# ADC.net
KiCad netlist of a schematic drawn in Altium Designer
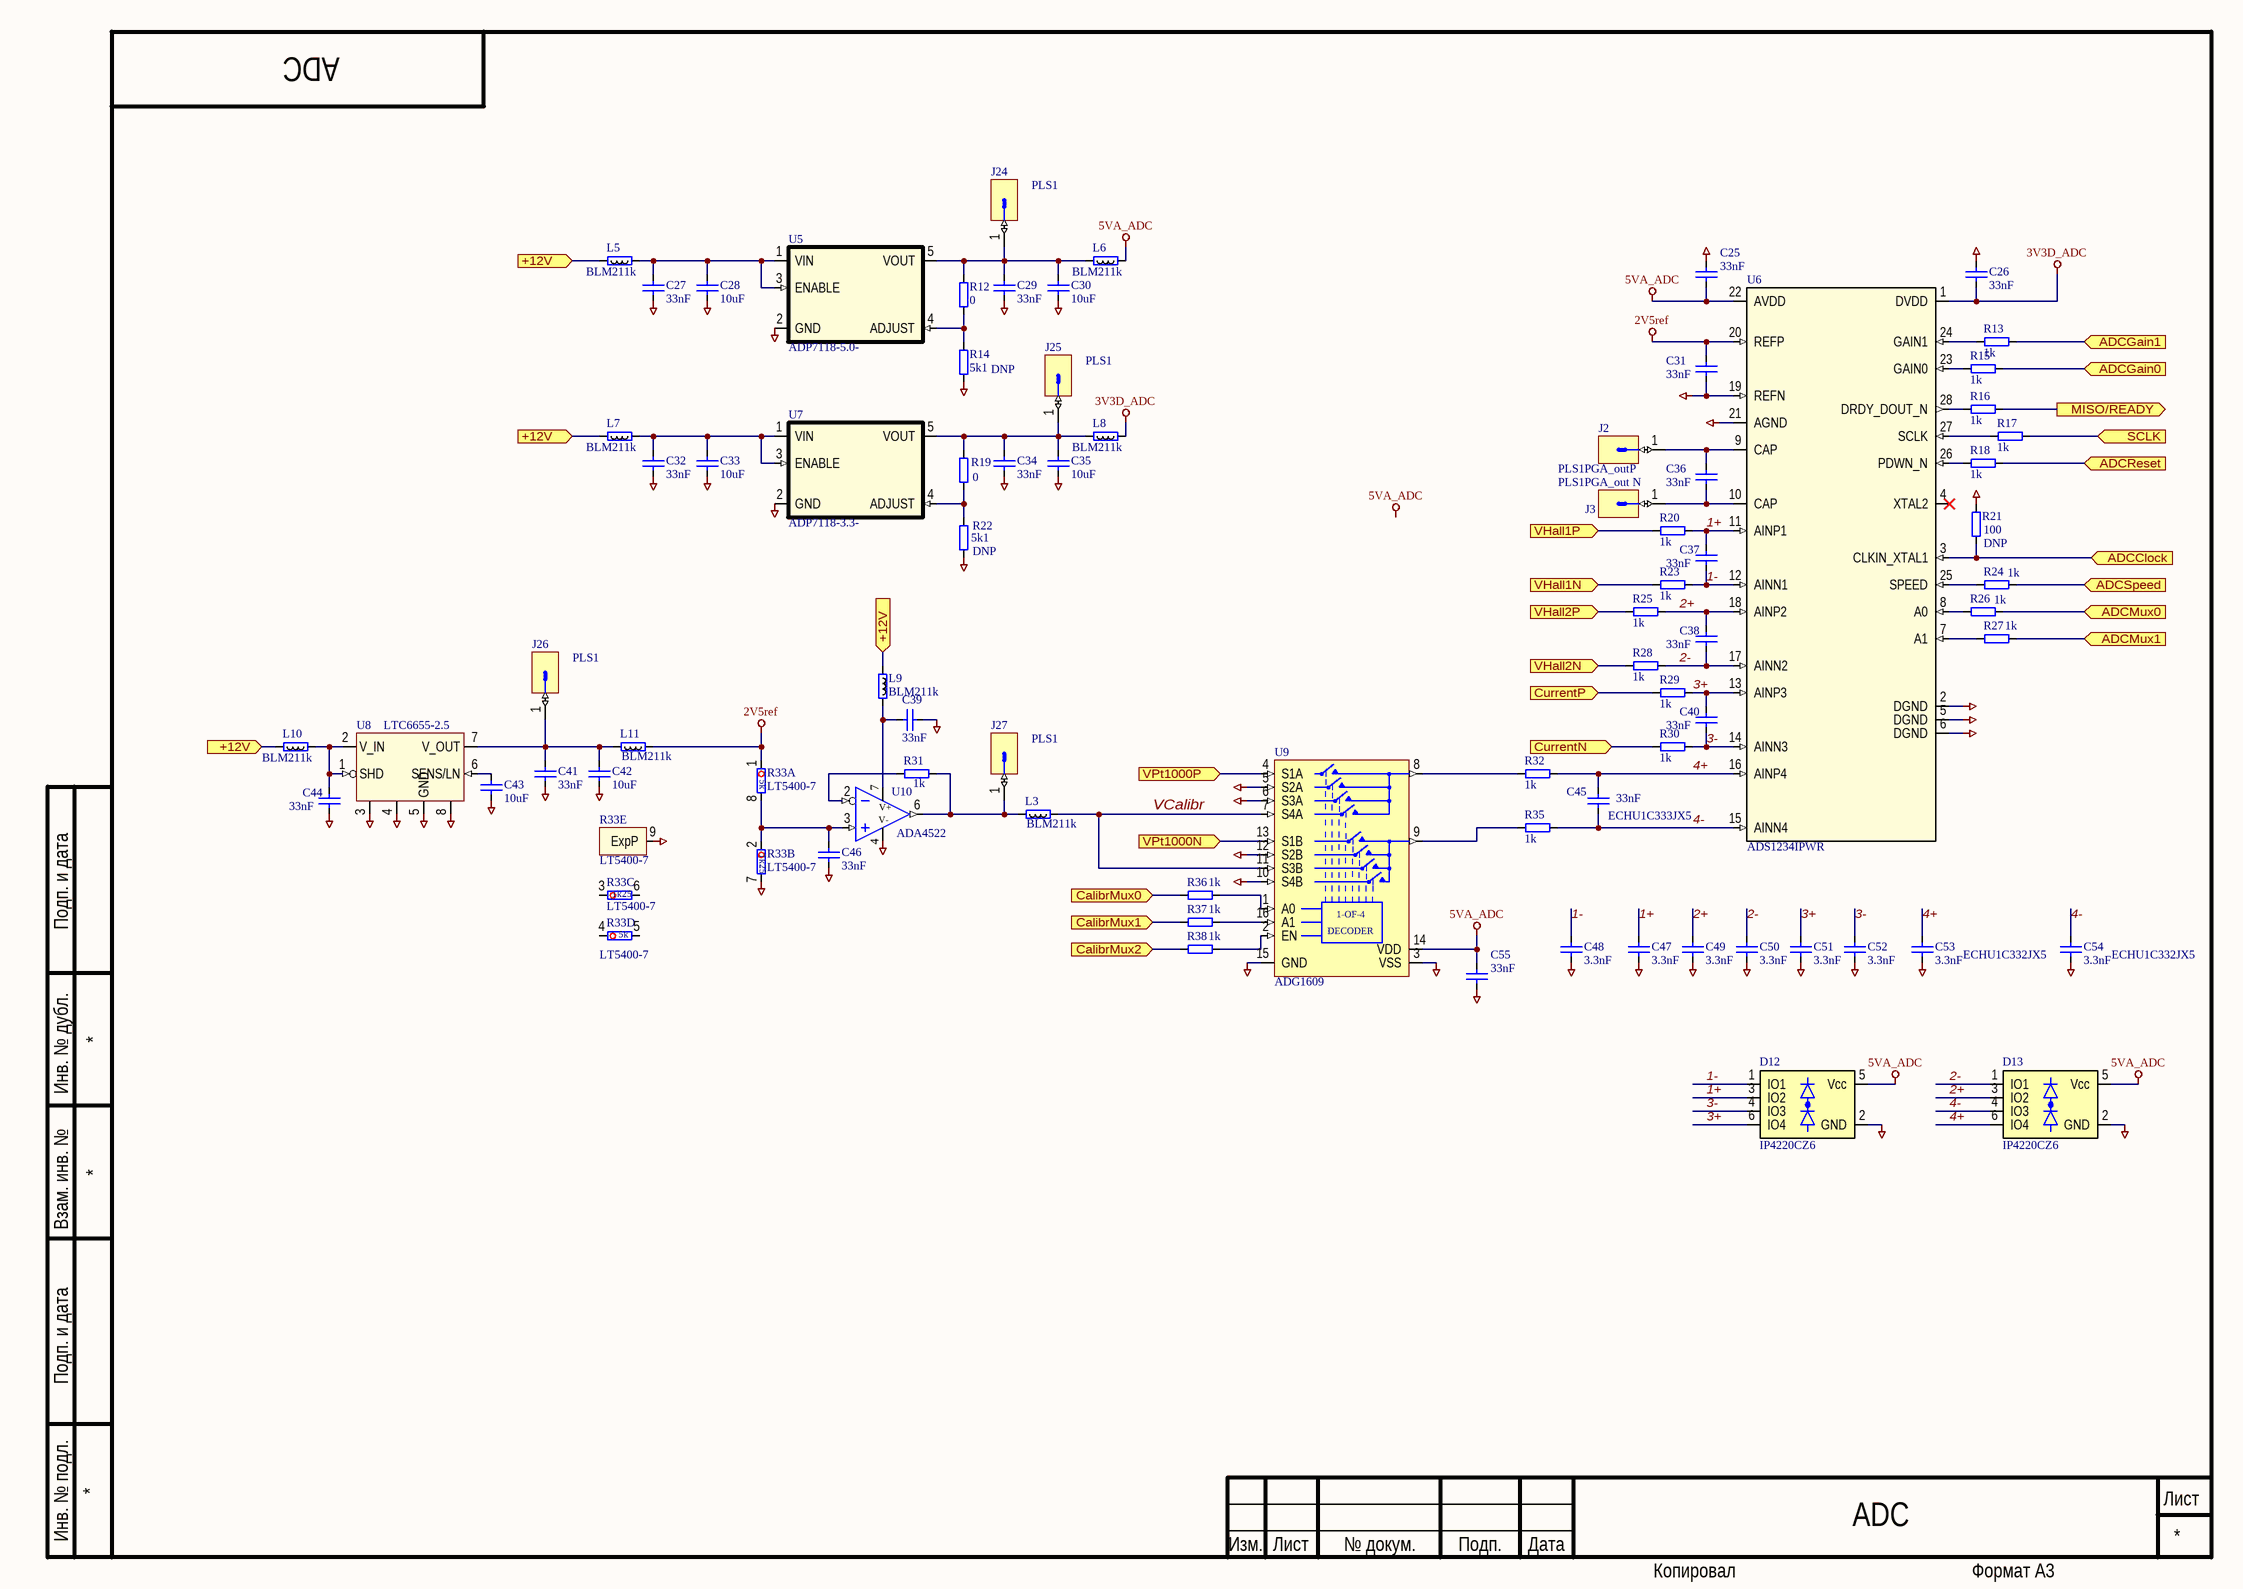
[diagram p0: ADC.SchDoc]

(export (version "E")
  (design (tool "Eeschema 10.0.6"))
  (components
    (comp (ref "C25")
      (value "33nF")
      (footprint "CAPC1608X87N")
      (description "Чип конденсатор 0603")
      (fields (field (name "VOLTAGE") "50V") (field (name "TOLERANCE") "20%"))
      (libsource (lib "DDSintLib") (part "C0603"))
    )
    (comp (ref "C26")
      (value "33nF")
      (footprint "CAPC1608X87N")
      (description "Чип конденсатор 0603")
      (fields (field (name "VOLTAGE") "50V") (field (name "TOLERANCE") "20%"))
      (libsource (lib "DDSintLib") (part "C0603"))
    )
    (comp (ref "C27")
      (value "33nF")
      (footprint "SMD0805CAP")
      (description "Чип конденсатор 0805")
      (fields (field (name "VOLTAGE") "25V") (field (name "TOLERANCE") "20%"))
      (libsource (lib "DDSintLib") (part "C0805"))
    )
    (comp (ref "C28")
      (value "10uF")
      (footprint "SMD0805CAP")
      (description "Чип конденсатор 0805")
      (fields (field (name "VOLTAGE") "25V") (field (name "TOLERANCE") "20%"))
      (libsource (lib "DDSintLib") (part "C0805"))
    )
    (comp (ref "C29")
      (value "33nF")
      (footprint "SMD0805CAP")
      (description "Чип конденсатор 0805")
      (fields (field (name "VOLTAGE") "25V") (field (name "TOLERANCE") "20%"))
      (libsource (lib "DDSintLib") (part "C0805"))
    )
    (comp (ref "C30")
      (value "10uF")
      (footprint "SMD0805CAP")
      (description "Чип конденсатор 0805")
      (fields (field (name "VOLTAGE") "25V") (field (name "TOLERANCE") "20%"))
      (libsource (lib "DDSintLib") (part "C0805"))
    )
    (comp (ref "C31")
      (value "33nF")
      (footprint "CAPC1608X87N")
      (description "Чип конденсатор 0603")
      (fields (field (name "VOLTAGE") "50V") (field (name "TOLERANCE") "20%"))
      (libsource (lib "DDSintLib") (part "C0603"))
    )
    (comp (ref "C32")
      (value "33nF")
      (footprint "SMD0805CAP")
      (description "Чип конденсатор 0805")
      (fields (field (name "VOLTAGE") "25V") (field (name "TOLERANCE") "20%"))
      (libsource (lib "DDSintLib") (part "C0805"))
    )
    (comp (ref "C33")
      (value "10uF")
      (footprint "SMD0805CAP")
      (description "Чип конденсатор 0805")
      (fields (field (name "VOLTAGE") "25V") (field (name "TOLERANCE") "20%"))
      (libsource (lib "DDSintLib") (part "C0805"))
    )
    (comp (ref "C34")
      (value "33nF")
      (footprint "SMD0805CAP")
      (description "Чип конденсатор 0805")
      (fields (field (name "VOLTAGE") "25V") (field (name "TOLERANCE") "20%"))
      (libsource (lib "DDSintLib") (part "C0805"))
    )
    (comp (ref "C35")
      (value "10uF")
      (footprint "SMD0805CAP")
      (description "Чип конденсатор 0805")
      (fields (field (name "VOLTAGE") "25V") (field (name "TOLERANCE") "20%"))
      (libsource (lib "DDSintLib") (part "C0805"))
    )
    (comp (ref "C36")
      (value "33nF")
      (footprint "CAPC1608X87N")
      (description "Чип конденсатор 0603")
      (fields (field (name "VOLTAGE") "50V") (field (name "TOLERANCE") "20%"))
      (libsource (lib "DDSintLib") (part "C0603"))
    )
    (comp (ref "C37")
      (value "33nF")
      (footprint "CAPC1608X87N")
      (description "Чип конденсатор 0603")
      (fields (field (name "VOLTAGE") "50V") (field (name "TOLERANCE") "20%"))
      (libsource (lib "DDSintLib") (part "C0603"))
    )
    (comp (ref "C38")
      (value "33nF")
      (footprint "CAPC1608X87N")
      (description "Чип конденсатор 0603")
      (fields (field (name "VOLTAGE") "50V") (field (name "TOLERANCE") "20%"))
      (libsource (lib "DDSintLib") (part "C0603"))
    )
    (comp (ref "C39")
      (value "33nF")
      (footprint "SMD0805CAP")
      (description "Чип конденсатор 0805")
      (fields (field (name "VOLTAGE") "25V") (field (name "TOLERANCE") "20%"))
      (libsource (lib "DDSintLib") (part "C0805"))
    )
    (comp (ref "C40")
      (value "33nF")
      (footprint "CAPC1608X87N")
      (description "Чип конденсатор 0603")
      (fields (field (name "VOLTAGE") "50V") (field (name "TOLERANCE") "20%"))
      (libsource (lib "DDSintLib") (part "C0603"))
    )
    (comp (ref "C41")
      (value "33nF")
      (footprint "SMD0805CAP")
      (description "Чип конденсатор 0805")
      (fields (field (name "VOLTAGE") "25V") (field (name "TOLERANCE") "20%"))
      (libsource (lib "DDSintLib") (part "C0805"))
    )
    (comp (ref "C42")
      (value "10uF")
      (footprint "SMD0805CAP")
      (description "Чип конденсатор 0805")
      (fields (field (name "VOLTAGE") "25V") (field (name "TOLERANCE") "20%"))
      (libsource (lib "DDSintLib") (part "C0805"))
    )
    (comp (ref "C43")
      (value "10uF")
      (footprint "SMD0805CAP")
      (description "Чип конденсатор 0805")
      (fields (field (name "VOLTAGE") "25V") (field (name "TOLERANCE") "20%"))
      (libsource (lib "DDSintLib") (part "C0805"))
    )
    (comp (ref "C44")
      (value "33nF")
      (footprint "SMD0805CAP")
      (description "Чип конденсатор 0805")
      (fields (field (name "VOLTAGE") "25V") (field (name "TOLERANCE") "20%"))
      (libsource (lib "DDSintLib") (part "C0805"))
    )
    (comp (ref "C45")
      (value "33nF")
      (footprint "CAPC1206")
      (description "Чип конденсатор 1206")
      (fields
        (field (name "VOLTAGE") "16V")
        (field (name "TOLERANCE") "1%")
        (field (name "NAME TO ORDER") "ECHU1C333JX5")
      )
      (libsource (lib "DDSintLib") (part "C1206"))
    )
    (comp (ref "C46")
      (value "33nF")
      (footprint "SMD0805CAP")
      (description "Чип конденсатор 0805")
      (fields (field (name "VOLTAGE") "25V") (field (name "TOLERANCE") "20%"))
      (libsource (lib "DDSintLib") (part "C0805"))
    )
    (comp (ref "C47")
      (value "3.3nF")
      (footprint "CAPC1608X87N")
      (description "Чип конденсатор 0603")
      (fields (field (name "VOLTAGE") "50V") (field (name "TOLERANCE") "20%"))
      (libsource (lib "DDSintLib") (part "C0603"))
    )
    (comp (ref "C48")
      (value "3.3nF")
      (footprint "CAPC1608X87N")
      (description "Чип конденсатор 0603")
      (fields (field (name "VOLTAGE") "50V") (field (name "TOLERANCE") "20%"))
      (libsource (lib "DDSintLib") (part "C0603"))
    )
    (comp (ref "C49")
      (value "3.3nF")
      (footprint "CAPC1608X87N")
      (description "Чип конденсатор 0603")
      (fields (field (name "VOLTAGE") "50V") (field (name "TOLERANCE") "20%"))
      (libsource (lib "DDSintLib") (part "C0603"))
    )
    (comp (ref "C50")
      (value "3.3nF")
      (footprint "CAPC1608X87N")
      (description "Чип конденсатор 0603")
      (fields (field (name "VOLTAGE") "50V") (field (name "TOLERANCE") "20%"))
      (libsource (lib "DDSintLib") (part "C0603"))
    )
    (comp (ref "C51")
      (value "3.3nF")
      (footprint "CAPC1608X87N")
      (description "Чип конденсатор 0603")
      (fields (field (name "VOLTAGE") "50V") (field (name "TOLERANCE") "20%"))
      (libsource (lib "DDSintLib") (part "C0603"))
    )
    (comp (ref "C52")
      (value "3.3nF")
      (footprint "CAPC1608X87N")
      (description "Чип конденсатор 0603")
      (fields (field (name "VOLTAGE") "50V") (field (name "TOLERANCE") "20%"))
      (libsource (lib "DDSintLib") (part "C0603"))
    )
    (comp (ref "C53")
      (value "3.3nF")
      (footprint "SMD0805CAP")
      (description "Чип конденсатор 0805")
      (fields
        (field (name "VOLTAGE") "25V")
        (field (name "TOLERANCE") "20%")
        (field (name "NAME TO ORDER") "ECHU1C332JX5")
      )
      (libsource (lib "DDSintLib") (part "C0805"))
    )
    (comp (ref "C54")
      (value "3.3nF")
      (footprint "SMD0805CAP")
      (description "Чип конденсатор 0805")
      (fields
        (field (name "VOLTAGE") "25V")
        (field (name "TOLERANCE") "20%")
        (field (name "NAME TO ORDER") "ECHU1C332JX5")
      )
      (libsource (lib "DDSintLib") (part "C0805"))
    )
    (comp (ref "C55")
      (value "33nF")
      (footprint "CAPC1608X87N")
      (description "Чип конденсатор 0603")
      (fields (field (name "VOLTAGE") "50V") (field (name "TOLERANCE") "20%"))
      (libsource (lib "DDSintLib") (part "C0603"))
    )
    (comp (ref "D12")
      (value "IP4220CZ6")
      (footprint "SOT95P270X145-6N")
      (description "Optotransistor")
      (fields (field (name "VOLTAGE") "6V"))
      (libsource (lib "DDSintLib") (part "IP4220"))
    )
    (comp (ref "D13")
      (value "IP4220CZ6")
      (footprint "SOT95P270X145-6N")
      (description "Optotransistor")
      (fields (field (name "VOLTAGE") "6V"))
      (libsource (lib "DDSintLib") (part "IP4220"))
    )
    (comp (ref "J2")
      (value "PLS1PGA_outP")
      (footprint "PLS1")
      (description "Штырь PLS1")
      (libsource (lib "") (part "PLS1_1"))
    )
    (comp (ref "J3")
      (value "PLS1PGA_out N")
      (footprint "PLS1")
      (description "Штырь PLS1")
      (libsource (lib "") (part "PLS1_1"))
    )
    (comp (ref "J24")
      (value "PLS1")
      (footprint "PLS1")
      (description "Штырь PLS1")
      (libsource (lib "DDSintLib") (part "PLS1"))
    )
    (comp (ref "J25")
      (value "PLS1")
      (footprint "PLS1")
      (description "Штырь PLS1")
      (libsource (lib "DDSintLib") (part "PLS1"))
    )
    (comp (ref "J26")
      (value "PLS1")
      (footprint "PLS1")
      (description "Штырь PLS1")
      (libsource (lib "DDSintLib") (part "PLS1"))
    )
    (comp (ref "J27")
      (value "PLS1")
      (footprint "PLS1")
      (description "Штырь PLS1")
      (libsource (lib "DDSintLib") (part "PLS1"))
    )
    (comp (ref "L3")
      (value "BLM211k")
      (footprint "RESC2012X50N")
      (description "SMD Ferrite bead 0805")
      (libsource (lib "DDSintLib") (part "BLM21"))
    )
    (comp (ref "L5")
      (value "BLM211k")
      (footprint "RESC2012X50N")
      (description "SMD Ferrite bead 0805")
      (libsource (lib "DDSintLib") (part "BLM21"))
    )
    (comp (ref "L6")
      (value "BLM211k")
      (footprint "RESC2012X50N")
      (description "SMD Ferrite bead 0805")
      (libsource (lib "DDSintLib") (part "BLM21"))
    )
    (comp (ref "L7")
      (value "BLM211k")
      (footprint "RESC2012X50N")
      (description "SMD Ferrite bead 0805")
      (libsource (lib "DDSintLib") (part "BLM21"))
    )
    (comp (ref "L8")
      (value "BLM211k")
      (footprint "RESC2012X50N")
      (description "SMD Ferrite bead 0805")
      (libsource (lib "DDSintLib") (part "BLM21"))
    )
    (comp (ref "L9")
      (value "BLM211k")
      (footprint "RESC2012X50N")
      (description "SMD Ferrite bead 0805")
      (libsource (lib "DDSintLib") (part "BLM21"))
    )
    (comp (ref "L10")
      (value "BLM211k")
      (footprint "RESC2012X50N")
      (description "SMD Ferrite bead 0805")
      (libsource (lib "DDSintLib") (part "BLM21"))
    )
    (comp (ref "L11")
      (value "BLM211k")
      (footprint "RESC2012X50N")
      (description "SMD Ferrite bead 0805")
      (libsource (lib "DDSintLib") (part "BLM21"))
    )
    (comp (ref "R12")
      (value "0")
      (footprint "SMD0805RES")
      (description "Чип резистор 0805")
      (fields (field (name "TOLERANCE") "1%"))
      (libsource (lib "DDSintLib") (part "R0805"))
    )
    (comp (ref "R13")
      (value "1k")
      (footprint "SMD0805RES")
      (description "Чип резистор 0805")
      (fields (field (name "TOLERANCE") "1%"))
      (libsource (lib "DDSintLib") (part "R0805"))
    )
    (comp (ref "R14")
      (value "5k1")
      (footprint "SMD0805RES")
      (description "Чип резистор 0805")
      (fields (field (name "SOLDER OPTION") "DNP") (field (name "TOLERANCE") "1%"))
      (libsource (lib "DDSintLib") (part "R0805"))
    )
    (comp (ref "R15")
      (value "1k")
      (footprint "SMD0805RES")
      (description "Чип резистор 0805")
      (fields (field (name "TOLERANCE") "1%"))
      (libsource (lib "DDSintLib") (part "R0805"))
    )
    (comp (ref "R16")
      (value "1k")
      (footprint "SMD0805RES")
      (description "Чип резистор 0805")
      (fields (field (name "TOLERANCE") "1%"))
      (libsource (lib "DDSintLib") (part "R0805"))
    )
    (comp (ref "R17")
      (value "1k")
      (footprint "SMD0805RES")
      (description "Чип резистор 0805")
      (fields (field (name "TOLERANCE") "1%"))
      (libsource (lib "DDSintLib") (part "R0805"))
    )
    (comp (ref "R18")
      (value "1k")
      (footprint "SMD0805RES")
      (description "Чип резистор 0805")
      (fields (field (name "TOLERANCE") "1%"))
      (libsource (lib "DDSintLib") (part "R0805"))
    )
    (comp (ref "R19")
      (value "0")
      (footprint "SMD0805RES")
      (description "Чип резистор 0805")
      (fields (field (name "TOLERANCE") "1%"))
      (libsource (lib "DDSintLib") (part "R0805"))
    )
    (comp (ref "R20")
      (value "1k")
      (footprint "SMD0805RES")
      (description "Чип резистор 0805")
      (fields (field (name "TOLERANCE") "1%"))
      (libsource (lib "DDSintLib") (part "R0805"))
    )
    (comp (ref "R21")
      (value "100")
      (footprint "SMD0805RES")
      (description "Чип резистор 0805")
      (fields (field (name "SOLDER OPTION") "DNP") (field (name "TOLERANCE") "1%"))
      (libsource (lib "DDSintLib") (part "R0805"))
    )
    (comp (ref "R22")
      (value "5k1")
      (footprint "SMD0805RES")
      (description "Чип резистор 0805")
      (fields (field (name "SOLDER OPTION") "DNP") (field (name "TOLERANCE") "1%"))
      (libsource (lib "DDSintLib") (part "R0805"))
    )
    (comp (ref "R23")
      (value "1k")
      (footprint "SMD0805RES")
      (description "Чип резистор 0805")
      (fields (field (name "TOLERANCE") "1%"))
      (libsource (lib "DDSintLib") (part "R0805"))
    )
    (comp (ref "R24")
      (value "1k")
      (footprint "SMD0805RES")
      (description "Чип резистор 0805")
      (fields (field (name "TOLERANCE") "1%"))
      (libsource (lib "DDSintLib") (part "R0805"))
    )
    (comp (ref "R25")
      (value "1k")
      (footprint "SMD0805RES")
      (description "Чип резистор 0805")
      (fields (field (name "TOLERANCE") "1%"))
      (libsource (lib "DDSintLib") (part "R0805"))
    )
    (comp (ref "R26")
      (value "1k")
      (footprint "SMD0805RES")
      (description "Чип резистор 0805")
      (fields (field (name "TOLERANCE") "1%"))
      (libsource (lib "DDSintLib") (part "R0805"))
    )
    (comp (ref "R27")
      (value "1k")
      (footprint "SMD0805RES")
      (description "Чип резистор 0805")
      (fields (field (name "TOLERANCE") "1%"))
      (libsource (lib "DDSintLib") (part "R0805"))
    )
    (comp (ref "R28")
      (value "1k")
      (footprint "SMD0805RES")
      (description "Чип резистор 0805")
      (fields (field (name "TOLERANCE") "1%"))
      (libsource (lib "DDSintLib") (part "R0805"))
    )
    (comp (ref "R29")
      (value "1k")
      (footprint "SMD0805RES")
      (description "Чип резистор 0805")
      (fields (field (name "TOLERANCE") "1%"))
      (libsource (lib "DDSintLib") (part "R0805"))
    )
    (comp (ref "R30")
      (value "1k")
      (footprint "SMD0805RES")
      (description "Чип резистор 0805")
      (fields (field (name "TOLERANCE") "1%"))
      (libsource (lib "DDSintLib") (part "R0805"))
    )
    (comp (ref "R31")
      (value "1k")
      (footprint "SMD0805RES")
      (description "Чип резистор 0805")
      (fields (field (name "TOLERANCE") "1%"))
      (libsource (lib "DDSintLib") (part "R0805"))
    )
    (comp (ref "R32")
      (value "1k")
      (footprint "SMD0805RES")
      (description "Чип резистор 0805")
      (fields (field (name "TOLERANCE") "1%"))
      (libsource (lib "DDSintLib") (part "R0805"))
    )
    (comp (ref "R33")
      (value "LT5400-7")
      (footprint "SOP65P488X110-9N-R178X241")
      (description "4 прецизионных резистора")
      (fields (field (name "TOLERANCE") "0..025%"))
      (libsource (lib "") (part "LT5400_7_1"))
    )
    (comp (ref "R35")
      (value "1k")
      (footprint "SMD0805RES")
      (description "Чип резистор 0805")
      (fields (field (name "TOLERANCE") "1%"))
      (libsource (lib "DDSintLib") (part "R0805"))
    )
    (comp (ref "R36")
      (value "1k")
      (footprint "SMD0805RES")
      (description "Чип резистор 0805")
      (fields (field (name "TOLERANCE") "1%"))
      (libsource (lib "DDSintLib") (part "R0805"))
    )
    (comp (ref "R37")
      (value "1k")
      (footprint "SMD0805RES")
      (description "Чип резистор 0805")
      (fields (field (name "TOLERANCE") "1%"))
      (libsource (lib "DDSintLib") (part "R0805"))
    )
    (comp (ref "R38")
      (value "1k")
      (footprint "SMD0805RES")
      (description "Чип резистор 0805")
      (fields (field (name "TOLERANCE") "1%"))
      (libsource (lib "DDSintLib") (part "R0805"))
    )
    (comp (ref "U5")
      (value "ADP7118-5.0-")
      (footprint "SOT23-5")
      (description "Positive LDO Linear stabilizer")
      (libsource (lib "DDSintLib") (part "ADP7118"))
    )
    (comp (ref "U6")
      (value "ADS1234IPWR")
      (footprint "SOP65P780X200-28N")
      (description "АЦП")
      (fields (field (name "VOLTAGE") "2V7 to 5V3"))
      (libsource (lib "DDS1") (part "ADS1234"))
    )
    (comp (ref "U7")
      (value "ADP7118-3.3-")
      (footprint "SOT23-5")
      (description "Positive LDO Linear stabilizer")
      (libsource (lib "DDSintLib") (part "ADP7118"))
    )
    (comp (ref "U8")
      (value "LTC6655-2.5")
      (footprint "DDS1:SOP65P488X110-8N")
      (description "Low noise precision reference,")
      (fields (field (name "VOLTAGE") "max13.2V"))
      (libsource (lib "DDS1") (part "LTC6655B-5"))
    )
    (comp (ref "U9")
      (value "ADG1609")
      (footprint "TSSOP-16")
      (description "Мультиплексор аналоговый дифференциальный 4 канала")
      (libsource (lib "DDSintLib") (part "ADG1609"))
    )
    (comp (ref "U10")
      (value "ADA4522")
      (footprint "SOP65P488X110-8N")
      (description "Op amp")
      (fields (field (name "VOLTAGE") "+-5 to +-27.5V"))
      (libsource (lib "DDS1") (part "ADA4522"))
    )
  )
  (nets
    (net (code "1") (name "/+12V") (class "Default")
      (node (ref "L10") (pin "1") (pinfunction "1_1") (pintype "passive"))
      (node (ref "L5") (pin "1") (pinfunction "1_1") (pintype "passive"))
      (node (ref "L7") (pin "1") (pinfunction "1_1") (pintype "passive"))
      (node (ref "L9") (pin "2") (pinfunction "2_2") (pintype "passive"))
    )
    (net (code "2") (name "/1+") (class "Default")
      (node (ref "C37") (pin "2") (pinfunction "2_2") (pintype "passive"))
      (node (ref "C47") (pin "2") (pinfunction "2_2") (pintype "passive"))
      (node (ref "D12") (pin "3") (pinfunction "IO2_3") (pintype "passive"))
      (node (ref "R20") (pin "2") (pinfunction "2_2") (pintype "passive"))
      (node (ref "U6") (pin "11") (pinfunction "AINP1_11") (pintype "input"))
    )
    (net (code "3") (name "/1-") (class "Default")
      (node (ref "C37") (pin "1") (pinfunction "1_1") (pintype "passive"))
      (node (ref "C48") (pin "2") (pinfunction "2_2") (pintype "passive"))
      (node (ref "D12") (pin "1") (pinfunction "IO1_1") (pintype "passive"))
      (node (ref "R23") (pin "2") (pinfunction "2_2") (pintype "passive"))
      (node (ref "U6") (pin "12") (pinfunction "AINN1_12") (pintype "input"))
    )
    (net (code "4") (name "/2+") (class "Default")
      (node (ref "C38") (pin "2") (pinfunction "2_2") (pintype "passive"))
      (node (ref "C49") (pin "2") (pinfunction "2_2") (pintype "passive"))
      (node (ref "D13") (pin "3") (pinfunction "IO2_3") (pintype "passive"))
      (node (ref "R25") (pin "2") (pinfunction "2_2") (pintype "passive"))
      (node (ref "U6") (pin "18") (pinfunction "AINP2_18") (pintype "input"))
    )
    (net (code "5") (name "/2-") (class "Default")
      (node (ref "C38") (pin "1") (pinfunction "1_1") (pintype "passive"))
      (node (ref "C50") (pin "2") (pinfunction "2_2") (pintype "passive"))
      (node (ref "D13") (pin "1") (pinfunction "IO1_1") (pintype "passive"))
      (node (ref "R28") (pin "2") (pinfunction "2_2") (pintype "passive"))
      (node (ref "U6") (pin "17") (pinfunction "AINN2_17") (pintype "input"))
    )
    (net (code "6") (name "/3+") (class "Default")
      (node (ref "C40") (pin "2") (pinfunction "2_2") (pintype "passive"))
      (node (ref "C51") (pin "2") (pinfunction "2_2") (pintype "passive"))
      (node (ref "D12") (pin "6") (pinfunction "IO4_6") (pintype "passive"))
      (node (ref "R29") (pin "2") (pinfunction "2_2") (pintype "passive"))
      (node (ref "U6") (pin "13") (pinfunction "AINP3_13") (pintype "input"))
    )
    (net (code "7") (name "/3-") (class "Default")
      (node (ref "C40") (pin "1") (pinfunction "1_1") (pintype "passive"))
      (node (ref "C52") (pin "2") (pinfunction "2_2") (pintype "passive"))
      (node (ref "D12") (pin "4") (pinfunction "IO3_4") (pintype "passive"))
      (node (ref "R30") (pin "2") (pinfunction "2_2") (pintype "passive"))
      (node (ref "U6") (pin "14") (pinfunction "AINN3_14") (pintype "input"))
    )
    (net (code "8") (name "/4+") (class "Default")
      (node (ref "C45") (pin "2") (pinfunction "2_2") (pintype "passive"))
      (node (ref "C53") (pin "2") (pinfunction "2_2") (pintype "passive"))
      (node (ref "D13") (pin "6") (pinfunction "IO4_6") (pintype "passive"))
      (node (ref "R32") (pin "2") (pinfunction "2_2") (pintype "passive"))
      (node (ref "U6") (pin "16") (pinfunction "AINP4_16") (pintype "input"))
    )
    (net (code "9") (name "/4-") (class "Default")
      (node (ref "C45") (pin "1") (pinfunction "1_1") (pintype "passive"))
      (node (ref "C54") (pin "2") (pinfunction "2_2") (pintype "passive"))
      (node (ref "D13") (pin "4") (pinfunction "IO3_4") (pintype "passive"))
      (node (ref "R35") (pin "2") (pinfunction "2_2") (pintype "passive"))
      (node (ref "U6") (pin "15") (pinfunction "AINN4_15") (pintype "input"))
    )
    (net (code "10") (name "/ADCClock") (class "Default")
      (node (ref "R21") (pin "1") (pinfunction "1_1") (pintype "passive"))
      (node (ref "U6") (pin "3") (pinfunction "CLKIN_XTAL1_3") (pintype "input"))
    )
    (net (code "11") (name "/ADCGain0") (class "Default")
      (node (ref "R15") (pin "2") (pinfunction "2_2") (pintype "passive"))
    )
    (net (code "12") (name "/ADCGain1") (class "Default")
      (node (ref "R13") (pin "2") (pinfunction "2_2") (pintype "passive"))
    )
    (net (code "13") (name "/ADCMux0") (class "Default")
      (node (ref "R26") (pin "2") (pinfunction "2_2") (pintype "passive"))
    )
    (net (code "14") (name "/ADCMux1") (class "Default")
      (node (ref "R27") (pin "2") (pinfunction "2_2") (pintype "passive"))
    )
    (net (code "15") (name "/ADCReset") (class "Default")
      (node (ref "R18") (pin "2") (pinfunction "2_2") (pintype "passive"))
    )
    (net (code "16") (name "/ADCSpeed") (class "Default")
      (node (ref "R24") (pin "2") (pinfunction "2_2") (pintype "passive"))
    )
    (net (code "17") (name "/CalibrMux0") (class "Default")
      (node (ref "R36") (pin "1") (pinfunction "1_1") (pintype "passive"))
    )
    (net (code "18") (name "/CalibrMux1") (class "Default")
      (node (ref "R37") (pin "1") (pinfunction "1_1") (pintype "passive"))
    )
    (net (code "19") (name "/CalibrMux2") (class "Default")
      (node (ref "R38") (pin "1") (pinfunction "1_1") (pintype "passive"))
    )
    (net (code "20") (name "/CurrentN") (class "Default")
      (node (ref "R30") (pin "1") (pinfunction "1_1") (pintype "passive"))
    )
    (net (code "21") (name "/CurrentP") (class "Default")
      (node (ref "R29") (pin "1") (pinfunction "1_1") (pintype "passive"))
    )
    (net (code "22") (name "/MISO{slash}READY") (class "Default")
      (node (ref "R16") (pin "2") (pinfunction "2_2") (pintype "passive"))
    )
    (net (code "23") (name "/SCLK") (class "Default")
      (node (ref "R17") (pin "2") (pinfunction "2_2") (pintype "passive"))
    )
    (net (code "24") (name "/VCalibr") (class "Default")
      (node (ref "L3") (pin "2") (pinfunction "2_2") (pintype "passive"))
      (node (ref "U9") (pin "11") (pinfunction "S3B_11") (pintype "input"))
      (node (ref "U9") (pin "7") (pinfunction "S4A_7") (pintype "input"))
    )
    (net (code "25") (name "/VHall1N") (class "Default")
      (node (ref "R23") (pin "1") (pinfunction "1_1") (pintype "passive"))
    )
    (net (code "26") (name "/VHall1P") (class "Default")
      (node (ref "R20") (pin "1") (pinfunction "1_1") (pintype "passive"))
    )
    (net (code "27") (name "/VHall2N") (class "Default")
      (node (ref "R28") (pin "1") (pinfunction "1_1") (pintype "passive"))
    )
    (net (code "28") (name "/VHall2P") (class "Default")
      (node (ref "R25") (pin "1") (pinfunction "1_1") (pintype "passive"))
    )
    (net (code "29") (name "/VPt1000N") (class "Default")
      (node (ref "U9") (pin "13") (pinfunction "S1B_13") (pintype "input"))
    )
    (net (code "30") (name "/VPt1000P") (class "Default")
      (node (ref "U9") (pin "4") (pinfunction "S1A_4") (pintype "input"))
    )
    (net (code "31") (name "2V5ref") (class "Default")
      (node (ref "C31") (pin "2") (pinfunction "2_2") (pintype "passive"))
      (node (ref "L11") (pin "2") (pinfunction "2_2") (pintype "passive"))
      (node (ref "R33") (pin "1") (pinfunction "1_1") (pintype "passive"))
      (node (ref "U6") (pin "20") (pinfunction "REFP_20") (pintype "input"))
    )
    (net (code "32") (name "3V3D_ADC") (class "Default")
      (node (ref "C26") (pin "1") (pinfunction "1_1") (pintype "passive"))
      (node (ref "L8") (pin "2") (pinfunction "2_2") (pintype "passive"))
      (node (ref "U6") (pin "1") (pinfunction "DVDD_1") (pintype "power_in"))
    )
    (net (code "33") (name "5VA_ADC") (class "Default")
      (node (ref "C25") (pin "1") (pinfunction "1_1") (pintype "passive"))
      (node (ref "C55") (pin "2") (pinfunction "2_2") (pintype "passive"))
      (node (ref "D12") (pin "5") (pinfunction "Vcc_5") (pintype "passive"))
      (node (ref "D13") (pin "5") (pinfunction "Vcc_5") (pintype "passive"))
      (node (ref "L6") (pin "2") (pinfunction "2_2") (pintype "passive"))
      (node (ref "U6") (pin "22") (pinfunction "AVDD_22") (pintype "power_in"))
      (node (ref "U9") (pin "14") (pinfunction "VDD_14") (pintype "power_in"))
    )
    (net (code "34") (name "GND") (class "Default")
      (node (ref "C25") (pin "2") (pinfunction "2_2") (pintype "passive"))
      (node (ref "C26") (pin "2") (pinfunction "2_2") (pintype "passive"))
      (node (ref "C27") (pin "1") (pinfunction "1_1") (pintype "passive"))
      (node (ref "C28") (pin "1") (pinfunction "1_1") (pintype "passive"))
      (node (ref "C29") (pin "1") (pinfunction "1_1") (pintype "passive"))
      (node (ref "C30") (pin "1") (pinfunction "1_1") (pintype "passive"))
      (node (ref "C31") (pin "1") (pinfunction "1_1") (pintype "passive"))
      (node (ref "C32") (pin "1") (pinfunction "1_1") (pintype "passive"))
      (node (ref "C33") (pin "1") (pinfunction "1_1") (pintype "passive"))
      (node (ref "C34") (pin "1") (pinfunction "1_1") (pintype "passive"))
      (node (ref "C35") (pin "1") (pinfunction "1_1") (pintype "passive"))
      (node (ref "C39") (pin "1") (pinfunction "1_1") (pintype "passive"))
      (node (ref "C41") (pin "1") (pinfunction "1_1") (pintype "passive"))
      (node (ref "C42") (pin "1") (pinfunction "1_1") (pintype "passive"))
      (node (ref "C43") (pin "1") (pinfunction "1_1") (pintype "passive"))
      (node (ref "C44") (pin "1") (pinfunction "1_1") (pintype "passive"))
      (node (ref "C46") (pin "1") (pinfunction "1_1") (pintype "passive"))
      (node (ref "C47") (pin "1") (pinfunction "1_1") (pintype "passive"))
      (node (ref "C48") (pin "1") (pinfunction "1_1") (pintype "passive"))
      (node (ref "C49") (pin "1") (pinfunction "1_1") (pintype "passive"))
      (node (ref "C50") (pin "1") (pinfunction "1_1") (pintype "passive"))
      (node (ref "C51") (pin "1") (pinfunction "1_1") (pintype "passive"))
      (node (ref "C52") (pin "1") (pinfunction "1_1") (pintype "passive"))
      (node (ref "C53") (pin "1") (pinfunction "1_1") (pintype "passive"))
      (node (ref "C54") (pin "1") (pinfunction "1_1") (pintype "passive"))
      (node (ref "C55") (pin "1") (pinfunction "1_1") (pintype "passive"))
      (node (ref "D12") (pin "2") (pinfunction "GND_2") (pintype "passive"))
      (node (ref "D13") (pin "2") (pinfunction "GND_2") (pintype "passive"))
      (node (ref "R14") (pin "1") (pinfunction "1_1") (pintype "passive"))
      (node (ref "R21") (pin "2") (pinfunction "2_2") (pintype "passive"))
      (node (ref "R22") (pin "1") (pinfunction "1_1") (pintype "passive"))
      (node (ref "R33") (pin "7") (pinfunction "7_7") (pintype "passive"))
      (node (ref "R33") (pin "9") (pinfunction "ExpP_9") (pintype "passive"))
      (node (ref "U10") (pin "4") (pinfunction "V-_4") (pintype "power_in"))
      (node (ref "U5") (pin "2") (pinfunction "GND_2") (pintype "power_in"))
      (node (ref "U6") (pin "19") (pinfunction "REFN_19") (pintype "input"))
      (node (ref "U6") (pin "2") (pinfunction "DGND_2") (pintype "power_in"))
      (node (ref "U6") (pin "21") (pinfunction "AGND_21") (pintype "power_in"))
      (node (ref "U6") (pin "5") (pinfunction "DGND_5") (pintype "power_in"))
      (node (ref "U6") (pin "6") (pinfunction "DGND_6") (pintype "power_in"))
      (node (ref "U7") (pin "2") (pinfunction "GND_2") (pintype "power_in"))
      (node (ref "U8") (pin "3") (pinfunction "GND_3") (pintype "passive"))
      (node (ref "U8") (pin "4") (pinfunction "GND_4") (pintype "passive"))
      (node (ref "U8") (pin "5") (pinfunction "GND_5") (pintype "passive"))
      (node (ref "U8") (pin "8") (pinfunction "GND_8") (pintype "power_in"))
      (node (ref "U9") (pin "10") (pinfunction "S4B_10") (pintype "input"))
      (node (ref "U9") (pin "12") (pinfunction "S2B_12") (pintype "input"))
      (node (ref "U9") (pin "15") (pinfunction "GND_15") (pintype "power_in"))
      (node (ref "U9") (pin "3") (pinfunction "VSS_3") (pintype "power_in"))
      (node (ref "U9") (pin "5") (pinfunction "S2A_5") (pintype "input"))
      (node (ref "U9") (pin "6") (pinfunction "S3A_6") (pintype "input"))
    )
    (net (code "35") (name "Net-(C36-Pad1)") (class "Default")
      (node (ref "C36") (pin "1") (pinfunction "1_1") (pintype "passive"))
      (node (ref "J3") (pin "1") (pinfunction "1_1") (pintype "bidirectional"))
      (node (ref "U6") (pin "10") (pinfunction "CAP_10") (pintype "passive"))
    )
    (net (code "36") (name "Net-(C36-Pad2)") (class "Default")
      (node (ref "C36") (pin "2") (pinfunction "2_2") (pintype "passive"))
      (node (ref "J2") (pin "1") (pinfunction "1_1") (pintype "bidirectional"))
      (node (ref "U6") (pin "9") (pinfunction "CAP_9") (pintype "passive"))
    )
    (net (code "37") (name "Net-(U5-ADJUST)") (class "Default")
      (node (ref "R12") (pin "1") (pinfunction "1_1") (pintype "passive"))
      (node (ref "R14") (pin "2") (pinfunction "2_2") (pintype "passive"))
      (node (ref "U5") (pin "4") (pinfunction "ADJUST_4") (pintype "input"))
    )
    (net (code "38") (name "Net-(U5-ENABLE)") (class "Default")
      (node (ref "C27") (pin "2") (pinfunction "2_2") (pintype "passive"))
      (node (ref "C28") (pin "2") (pinfunction "2_2") (pintype "passive"))
      (node (ref "L5") (pin "2") (pinfunction "2_2") (pintype "passive"))
      (node (ref "U5") (pin "1") (pinfunction "VIN_1") (pintype "power_in"))
      (node (ref "U5") (pin "3") (pinfunction "ENABLE_3") (pintype "input"))
    )
    (net (code "39") (name "Net-(U5-VOUT)") (class "Default")
      (node (ref "C29") (pin "2") (pinfunction "2_2") (pintype "passive"))
      (node (ref "C30") (pin "2") (pinfunction "2_2") (pintype "passive"))
      (node (ref "J24") (pin "1") (pinfunction "1_1") (pintype "bidirectional"))
      (node (ref "L6") (pin "1") (pinfunction "1_1") (pintype "passive"))
      (node (ref "R12") (pin "2") (pinfunction "2_2") (pintype "passive"))
      (node (ref "U5") (pin "5") (pinfunction "VOUT_5") (pintype "power_in"))
    )
    (net (code "40") (name "Net-(U6-A0)") (class "Default")
      (node (ref "R26") (pin "1") (pinfunction "1_1") (pintype "passive"))
      (node (ref "U6") (pin "8") (pinfunction "A0_8") (pintype "input"))
    )
    (net (code "41") (name "Net-(U6-A1)") (class "Default")
      (node (ref "R27") (pin "1") (pinfunction "1_1") (pintype "passive"))
      (node (ref "U6") (pin "7") (pinfunction "A1_7") (pintype "input"))
    )
    (net (code "42") (name "Net-(U6-DRDY_DOUT_N)") (class "Default")
      (node (ref "R16") (pin "1") (pinfunction "1_1") (pintype "passive"))
      (node (ref "U6") (pin "28") (pinfunction "DRDY_DOUT_N_28") (pintype "output"))
    )
    (net (code "43") (name "Net-(U6-GAIN0)") (class "Default")
      (node (ref "R15") (pin "1") (pinfunction "1_1") (pintype "passive"))
      (node (ref "U6") (pin "23") (pinfunction "GAIN0_23") (pintype "input"))
    )
    (net (code "44") (name "Net-(U6-GAIN1)") (class "Default")
      (node (ref "R13") (pin "1") (pinfunction "1_1") (pintype "passive"))
      (node (ref "U6") (pin "24") (pinfunction "GAIN1_24") (pintype "input"))
    )
    (net (code "45") (name "Net-(U6-PDWN_N)") (class "Default")
      (node (ref "R18") (pin "1") (pinfunction "1_1") (pintype "passive"))
      (node (ref "U6") (pin "26") (pinfunction "PDWN_N_26") (pintype "input"))
    )
    (net (code "46") (name "Net-(U6-SCLK)") (class "Default")
      (node (ref "R17") (pin "1") (pinfunction "1_1") (pintype "passive"))
      (node (ref "U6") (pin "27") (pinfunction "SCLK_27") (pintype "input"))
    )
    (net (code "47") (name "Net-(U6-SPEED)") (class "Default")
      (node (ref "R24") (pin "1") (pinfunction "1_1") (pintype "passive"))
      (node (ref "U6") (pin "25") (pinfunction "SPEED_25") (pintype "input"))
    )
    (net (code "48") (name "Net-(U7-ADJUST)") (class "Default")
      (node (ref "R19") (pin "1") (pinfunction "1_1") (pintype "passive"))
      (node (ref "R22") (pin "2") (pinfunction "2_2") (pintype "passive"))
      (node (ref "U7") (pin "4") (pinfunction "ADJUST_4") (pintype "input"))
    )
    (net (code "49") (name "Net-(U7-ENABLE)") (class "Default")
      (node (ref "C32") (pin "2") (pinfunction "2_2") (pintype "passive"))
      (node (ref "C33") (pin "2") (pinfunction "2_2") (pintype "passive"))
      (node (ref "L7") (pin "2") (pinfunction "2_2") (pintype "passive"))
      (node (ref "U7") (pin "1") (pinfunction "VIN_1") (pintype "power_in"))
      (node (ref "U7") (pin "3") (pinfunction "ENABLE_3") (pintype "input"))
    )
    (net (code "50") (name "Net-(U7-VOUT)") (class "Default")
      (node (ref "C34") (pin "2") (pinfunction "2_2") (pintype "passive"))
      (node (ref "C35") (pin "2") (pinfunction "2_2") (pintype "passive"))
      (node (ref "J25") (pin "1") (pinfunction "1_1") (pintype "bidirectional"))
      (node (ref "L8") (pin "1") (pinfunction "1_1") (pintype "passive"))
      (node (ref "R19") (pin "2") (pinfunction "2_2") (pintype "passive"))
      (node (ref "U7") (pin "5") (pinfunction "VOUT_5") (pintype "power_in"))
    )
    (net (code "51") (name "Net-(U8-SENS{slash}LN)") (class "Default")
      (node (ref "C43") (pin "2") (pinfunction "2_2") (pintype "passive"))
      (node (ref "U8") (pin "6") (pinfunction "SENS/LN_6") (pintype "input"))
    )
    (net (code "52") (name "Net-(U8-SHD)") (class "Default")
      (node (ref "C44") (pin "2") (pinfunction "2_2") (pintype "passive"))
      (node (ref "L10") (pin "2") (pinfunction "2_2") (pintype "passive"))
      (node (ref "U8") (pin "1") (pinfunction "SHD_1") (pintype "input"))
      (node (ref "U8") (pin "2") (pinfunction "V_IN_2") (pintype "power_in"))
    )
    (net (code "53") (name "Net-(U8-V_OUT)") (class "Default")
      (node (ref "C41") (pin "2") (pinfunction "2_2") (pintype "passive"))
      (node (ref "C42") (pin "2") (pinfunction "2_2") (pintype "passive"))
      (node (ref "J26") (pin "1") (pinfunction "1_1") (pintype "bidirectional"))
      (node (ref "L11") (pin "1") (pinfunction "1_1") (pintype "passive"))
      (node (ref "U8") (pin "7") (pinfunction "V_OUT_7") (pintype "passive"))
    )
    (net (code "54") (name "Net-(U9-A0)") (class "Default")
      (node (ref "R36") (pin "2") (pinfunction "2_2") (pintype "passive"))
      (node (ref "U9") (pin "1") (pinfunction "A0_1") (pintype "input"))
    )
    (net (code "55") (name "Net-(U9-A1)") (class "Default")
      (node (ref "R37") (pin "2") (pinfunction "2_2") (pintype "passive"))
      (node (ref "U9") (pin "16") (pinfunction "A1_16") (pintype "input"))
    )
    (net (code "56") (name "Net-(U9-DA)") (class "Default")
      (node (ref "R32") (pin "1") (pinfunction "1_1") (pintype "passive"))
      (node (ref "U9") (pin "8") (pinfunction "DA_8") (pintype "output"))
    )
    (net (code "57") (name "Net-(U9-DB)") (class "Default")
      (node (ref "R35") (pin "1") (pinfunction "1_1") (pintype "passive"))
      (node (ref "U9") (pin "9") (pinfunction "DB_9") (pintype "output"))
    )
    (net (code "58") (name "Net-(U9-EN)") (class "Default")
      (node (ref "R38") (pin "2") (pinfunction "2_2") (pintype "passive"))
      (node (ref "U9") (pin "2") (pinfunction "EN_2") (pintype "input"))
    )
    (net (code "59") (name "Net-(U10-IN+)") (class "Default")
      (node (ref "C46") (pin "2") (pinfunction "2_2") (pintype "passive"))
      (node (ref "R33") (pin "2") (pinfunction "2_2") (pintype "passive"))
      (node (ref "R33") (pin "8") (pinfunction "8_8") (pintype "passive"))
      (node (ref "U10") (pin "3") (pinfunction "IN+_3") (pintype "input"))
    )
    (net (code "60") (name "Net-(U10-IN-)") (class "Default")
      (node (ref "R31") (pin "1") (pinfunction "1_1") (pintype "passive"))
      (node (ref "U10") (pin "2") (pinfunction "IN-_2") (pintype "input"))
    )
    (net (code "61") (name "Net-(U10-OUT)") (class "Default")
      (node (ref "J27") (pin "1") (pinfunction "1_1") (pintype "bidirectional"))
      (node (ref "L3") (pin "1") (pinfunction "1_1") (pintype "passive"))
      (node (ref "R31") (pin "2") (pinfunction "2_2") (pintype "passive"))
      (node (ref "U10") (pin "6") (pinfunction "OUT_6") (pintype "output"))
    )
    (net (code "62") (name "Net-(U10-V+)") (class "Default")
      (node (ref "C39") (pin "2") (pinfunction "2_2") (pintype "passive"))
      (node (ref "L9") (pin "1") (pinfunction "1_1") (pintype "passive"))
      (node (ref "U10") (pin "7") (pinfunction "V+_7") (pintype "power_in"))
    )
    (net (code "63") (name "unconnected-(R33-Pad3)") (class "Default")
      (node (ref "R33") (pin "3") (pinfunction "3_3") (pintype "passive"))
    )
    (net (code "64") (name "unconnected-(R33-Pad4)") (class "Default")
      (node (ref "R33") (pin "4") (pinfunction "4_4") (pintype "passive"))
    )
    (net (code "65") (name "unconnected-(R33-Pad5)") (class "Default")
      (node (ref "R33") (pin "5") (pinfunction "5_5") (pintype "passive"))
    )
    (net (code "66") (name "unconnected-(R33-Pad6)") (class "Default")
      (node (ref "R33") (pin "6") (pinfunction "6_6") (pintype "passive"))
    )
    (net (code "67") (name "unconnected-(U6-XTAL2-Pad4)") (class "Default")
      (node (ref "U6") (pin "4") (pinfunction "XTAL2_4") (pintype "passive+no_connect"))
    )
  )
)
